# W682X.net
KiCad netlist of a schematic drawn in EAGLE
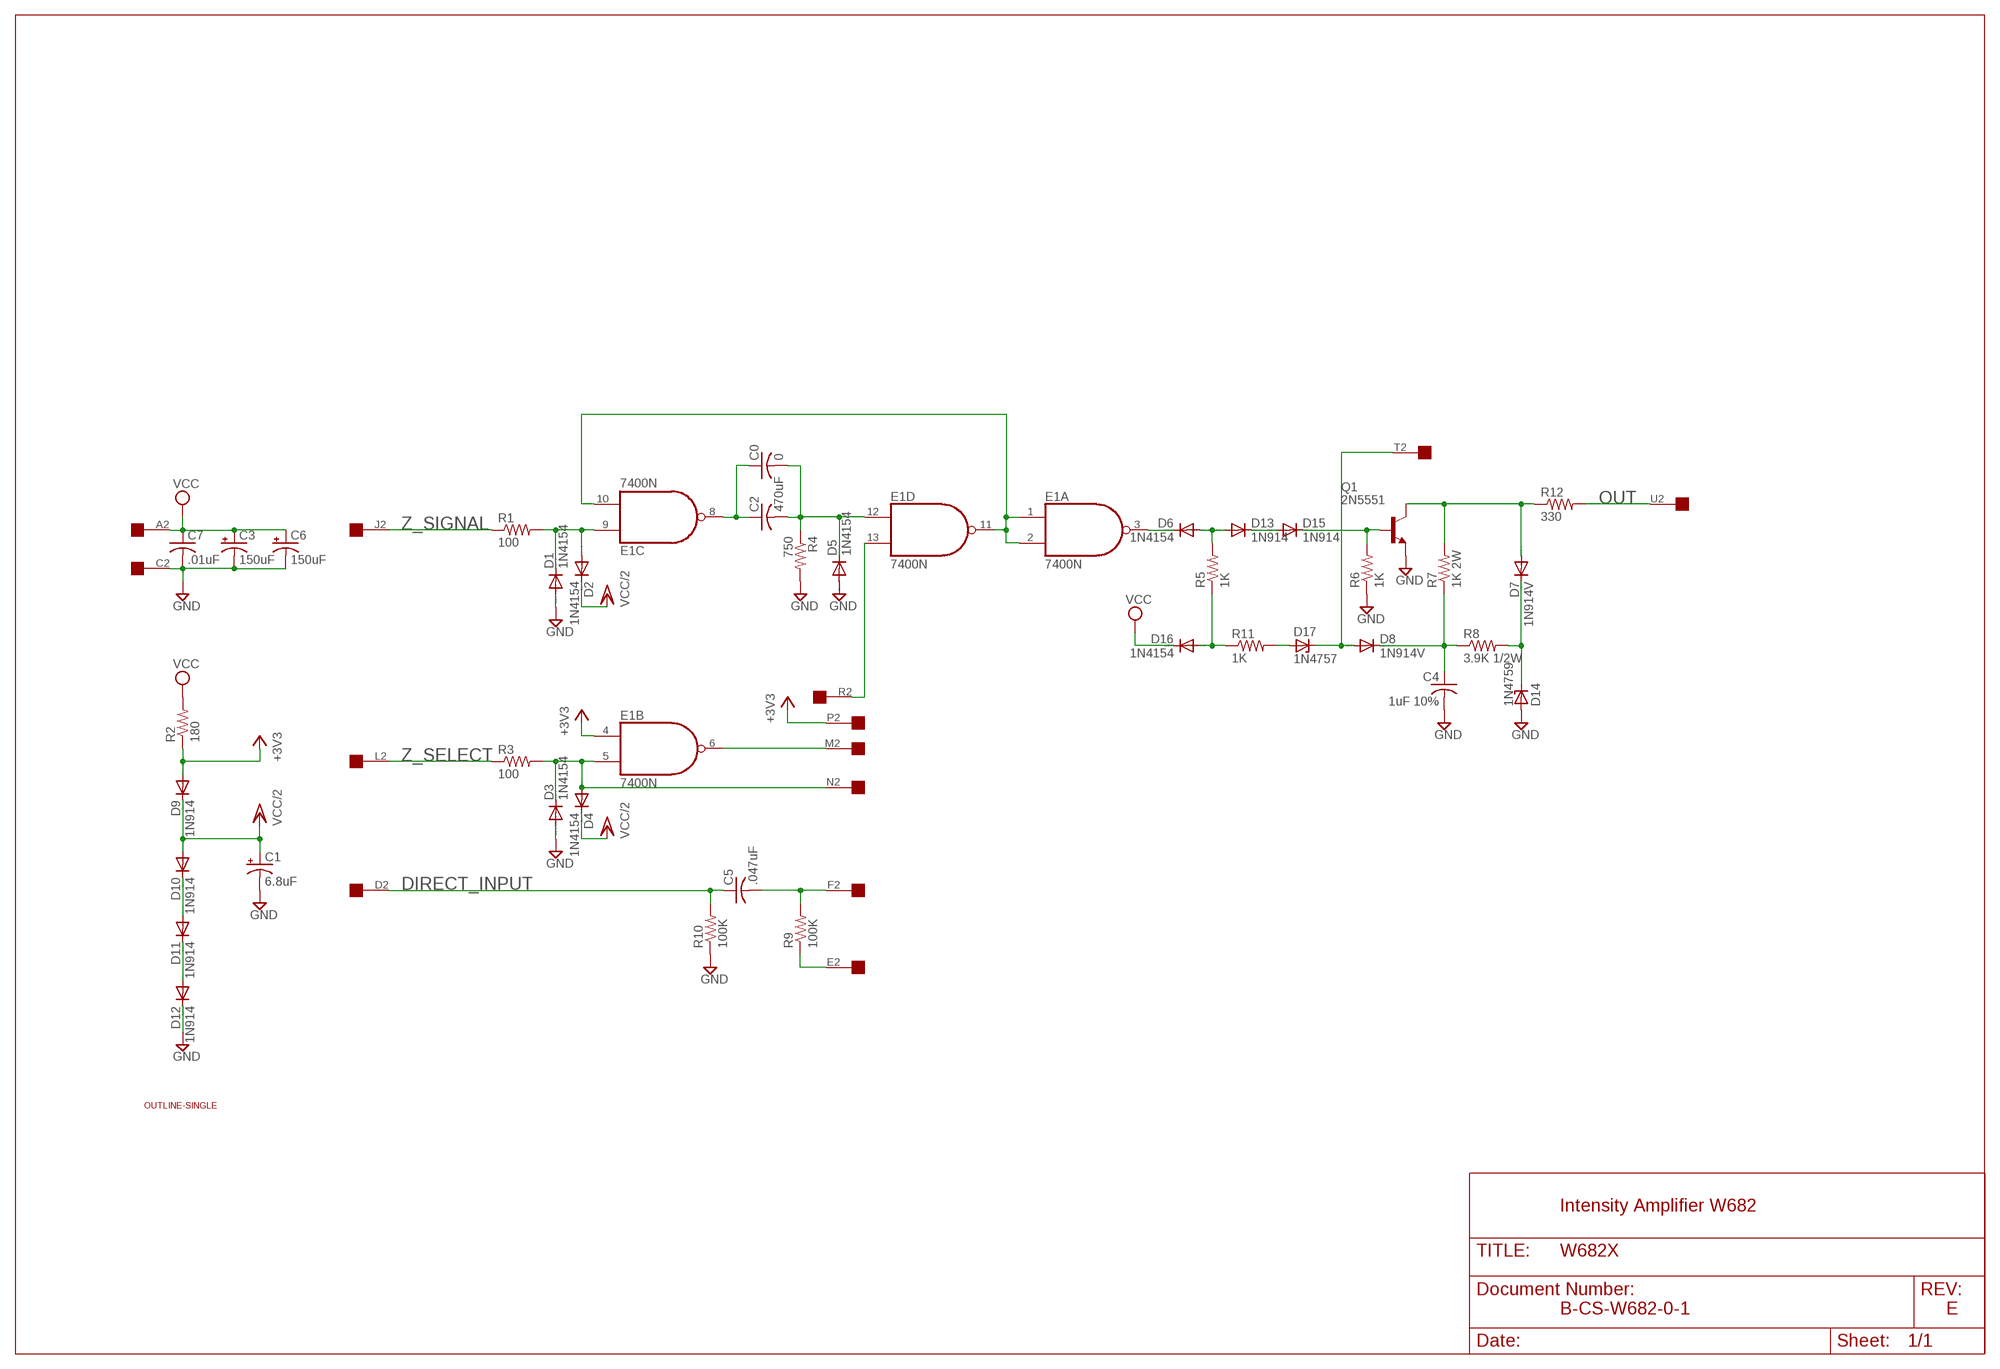
[diagram p0: schematic, sheet 1]

(export (version "E")
  (design (tool "Eeschema 10.0.6"))
  (components
    (comp (ref "C0")
      (value "0")
      (footprint "eagle-import:C050-025X075")
      (libsource (lib "eagle-import") (part "C-US050-025X075"))
    )
    (comp (ref "C1")
      (value "6.8uF")
      (footprint "eagle-import:E12-8")
      (libsource (lib "eagle-import") (part "CPOL-USE20-8AXIAL"))
    )
    (comp (ref "C2")
      (value "470uF")
      (footprint "eagle-import:C050-025X075")
      (libsource (lib "eagle-import") (part "C-US050-025X075"))
    )
    (comp (ref "C3")
      (value "150uF")
      (footprint "eagle-import:E22-9")
      (libsource (lib "eagle-import") (part "CPOL-USE22-9AXIAL"))
    )
    (comp (ref "C4")
      (value "1uF 10%")
      (footprint "eagle-import:C325-137X374")
      (libsource (lib "eagle-import") (part "C-US325-137X374"))
    )
    (comp (ref "C5")
      (value ".047uF")
      (footprint "eagle-import:C275-093X316")
      (libsource (lib "eagle-import") (part "C-US275-093X316"))
    )
    (comp (ref "C6")
      (value "150uF")
      (footprint "eagle-import:E22-9")
      (libsource (lib "eagle-import") (part "CPOL-USE22-9AXIAL"))
    )
    (comp (ref "C7")
      (value ".01uF")
      (footprint "eagle-import:C050-025X075")
      (libsource (lib "eagle-import") (part "C-US050-025X075"))
    )
    (comp (ref "D1")
      (value "1N4154")
      (footprint "eagle-import:DO35-10")
      (libsource (lib "eagle-import") (part "DIODE-DO35-10"))
    )
    (comp (ref "D2")
      (value "1N4154")
      (footprint "eagle-import:DO35-10")
      (libsource (lib "eagle-import") (part "DIODE-DO35-10"))
    )
    (comp (ref "D3")
      (value "1N4154")
      (footprint "eagle-import:DO35-10")
      (libsource (lib "eagle-import") (part "DIODE-DO35-10"))
    )
    (comp (ref "D4")
      (value "1N4154")
      (footprint "eagle-import:DO35-10")
      (libsource (lib "eagle-import") (part "DIODE-DO35-10"))
    )
    (comp (ref "D5")
      (value "1N4154")
      (footprint "eagle-import:DO35-10")
      (libsource (lib "eagle-import") (part "DIODE-DO35-10"))
    )
    (comp (ref "D6")
      (value "1N4154")
      (footprint "eagle-import:DO35-10")
      (libsource (lib "eagle-import") (part "DIODE-DO35-10"))
    )
    (comp (ref "D7")
      (value "1N914V")
      (footprint "eagle-import:DO41-10")
      (libsource (lib "eagle-import") (part "DIODE-DO41-10"))
    )
    (comp (ref "D8")
      (value "1N914V")
      (footprint "eagle-import:DO41-10")
      (libsource (lib "eagle-import") (part "DIODE-DO41-10"))
    )
    (comp (ref "D9")
      (value "1N914")
      (footprint "eagle-import:DO35-10")
      (libsource (lib "eagle-import") (part "DIODE-DO35-10"))
    )
    (comp (ref "D10")
      (value "1N914")
      (footprint "eagle-import:DO35-10")
      (libsource (lib "eagle-import") (part "DIODE-DO35-10"))
    )
    (comp (ref "D11")
      (value "1N914")
      (footprint "eagle-import:DO35-10")
      (libsource (lib "eagle-import") (part "DIODE-DO35-10"))
    )
    (comp (ref "D12")
      (value "1N914")
      (footprint "eagle-import:DO35-10")
      (libsource (lib "eagle-import") (part "DIODE-DO35-10"))
    )
    (comp (ref "D13")
      (value "1N914")
      (footprint "eagle-import:DO35-10")
      (libsource (lib "eagle-import") (part "DIODE-DO35-10"))
    )
    (comp (ref "D14")
      (value "1N4759")
      (footprint "eagle-import:ZDIO12.5")
      (libsource (lib "eagle-import") (part "ZENER-DIODEZD-12.5"))
    )
    (comp (ref "D15")
      (value "1N914")
      (footprint "eagle-import:DO35-10")
      (libsource (lib "eagle-import") (part "DIODE-DO35-10"))
    )
    (comp (ref "D16")
      (value "1N4154")
      (footprint "eagle-import:DO35-10")
      (libsource (lib "eagle-import") (part "DIODE-DO35-10"))
    )
    (comp (ref "D17")
      (value "1N4757")
      (footprint "eagle-import:ZDIO12.5")
      (libsource (lib "eagle-import") (part "ZENER-DIODEZD-12.5"))
    )
    (comp (ref "E1")
      (value "7400N")
      (footprint "eagle-import:DIL14")
      (libsource (lib "eagle-import") (part "7400N"))
    )
    (comp (ref "Q1")
      (value "2N5551")
      (footprint "eagle-import:TO39")
      (libsource (lib "eagle-import") (part "-NPN-TO39-EBC2N2102"))
    )
    (comp (ref "R1")
      (value "100")
      (footprint "eagle-import:0207_10")
      (libsource (lib "eagle-import") (part "R-US_0207/10"))
    )
    (comp (ref "R2")
      (value "180")
      (footprint "eagle-import:0207_10")
      (libsource (lib "eagle-import") (part "R-US_0207/10"))
    )
    (comp (ref "R3")
      (value "100")
      (footprint "eagle-import:0207_10")
      (libsource (lib "eagle-import") (part "R-US_0207/10"))
    )
    (comp (ref "R4")
      (value "750")
      (footprint "eagle-import:0207_10")
      (libsource (lib "eagle-import") (part "R-US_0207/10"))
    )
    (comp (ref "R5")
      (value "1K")
      (footprint "eagle-import:0207_10")
      (libsource (lib "eagle-import") (part "R-US_0207/10"))
    )
    (comp (ref "R6")
      (value "1K")
      (footprint "eagle-import:0207_10")
      (libsource (lib "eagle-import") (part "R-US_0207/10"))
    )
    (comp (ref "R7")
      (value "1K 2W")
      (footprint "eagle-import:0818_25")
      (libsource (lib "eagle-import") (part "R-US_0818/25"))
    )
    (comp (ref "R8")
      (value "3.9K 1/2W")
      (footprint "eagle-import:0411_15")
      (libsource (lib "eagle-import") (part "R-US_0411/15"))
    )
    (comp (ref "R9")
      (value "100K")
      (footprint "eagle-import:0207_10")
      (libsource (lib "eagle-import") (part "R-US_0207/10"))
    )
    (comp (ref "R10")
      (value "100K")
      (footprint "eagle-import:0207_10")
      (libsource (lib "eagle-import") (part "R-US_0207/10"))
    )
    (comp (ref "R11")
      (value "1K")
      (footprint "eagle-import:0207_10")
      (libsource (lib "eagle-import") (part "R-US_0207/10"))
    )
    (comp (ref "R12")
      (value "330")
      (footprint "eagle-import:0207_10")
      (libsource (lib "eagle-import") (part "R-US_0207/10"))
    )
    (comp (ref "U$1")
      (value "OUTLINE-SINGLE")
      (footprint "eagle-import:SINGLE")
      (libsource (lib "eagle-import") (part "OUTLINE-SINGLE"))
    )
    (comp (ref "U$2")
      (value "EDGE-1")
      (footprint "eagle-import:EDGE-CON1")
      (libsource (lib "eagle-import") (part "EDGE-1"))
    )
  )
  (nets
    (net (code "1") (name "+3V3") (class "Default")
      (node (ref "D9") (pin "A") (pinfunction "A_A") (pintype "passive"))
      (node (ref "E1") (pin "4") (pinfunction "I0_4") (pintype "input"))
      (node (ref "R2") (pin "1") (pinfunction "1_1") (pintype "passive"))
      (node (ref "U$2") (pin "P2") (pinfunction "1_P2") (pintype "bidirectional"))
    )
    (net (code "2") (name "/DIRECT_INPUT") (class "Default")
      (node (ref "C5") (pin "1") (pinfunction "1_1") (pintype "passive"))
      (node (ref "R10") (pin "2") (pinfunction "2_2") (pintype "passive"))
      (node (ref "U$2") (pin "D2") (pinfunction "1_D2") (pintype "bidirectional"))
    )
    (net (code "3") (name "/OUT") (class "Default")
      (node (ref "R12") (pin "2") (pinfunction "2_2") (pintype "passive"))
      (node (ref "U$2") (pin "U2") (pinfunction "1_U2") (pintype "bidirectional"))
    )
    (net (code "4") (name "/Z_SELECT") (class "Default")
      (node (ref "R3") (pin "1") (pinfunction "1_1") (pintype "passive"))
      (node (ref "U$2") (pin "L2") (pinfunction "1_L2") (pintype "bidirectional"))
    )
    (net (code "5") (name "/Z_SIGNAL") (class "Default")
      (node (ref "R1") (pin "1") (pinfunction "1_1") (pintype "passive"))
      (node (ref "U$2") (pin "J2") (pinfunction "1_J2") (pintype "bidirectional"))
    )
    (net (code "6") (name "GND") (class "Default")
      (node (ref "C1") (pin "-") (pinfunction "-_-") (pintype "passive"))
      (node (ref "C3") (pin "-") (pinfunction "-_-") (pintype "passive"))
      (node (ref "C4") (pin "2") (pinfunction "2_2") (pintype "passive"))
      (node (ref "C6") (pin "-") (pinfunction "-_-") (pintype "passive"))
      (node (ref "C7") (pin "2") (pinfunction "2_2") (pintype "passive"))
      (node (ref "D1") (pin "A") (pinfunction "A_A") (pintype "passive"))
      (node (ref "D12") (pin "C") (pinfunction "C_C") (pintype "passive"))
      (node (ref "D14") (pin "A") (pinfunction "A_A") (pintype "passive"))
      (node (ref "D3") (pin "A") (pinfunction "A_A") (pintype "passive"))
      (node (ref "D5") (pin "A") (pinfunction "A_A") (pintype "passive"))
      (node (ref "Q1") (pin "1") (pinfunction "E_1") (pintype "passive"))
      (node (ref "R10") (pin "1") (pinfunction "1_1") (pintype "passive"))
      (node (ref "R4") (pin "2") (pinfunction "2_2") (pintype "passive"))
      (node (ref "R6") (pin "1") (pinfunction "1_1") (pintype "passive"))
      (node (ref "U$2") (pin "C2") (pinfunction "1_C2") (pintype "bidirectional"))
    )
    (net (code "7") (name "Net-(C4-Pad1)") (class "Default")
      (node (ref "C4") (pin "1") (pinfunction "1_1") (pintype "passive"))
      (node (ref "D8") (pin "C") (pinfunction "C_C") (pintype "passive"))
      (node (ref "R7") (pin "1") (pinfunction "1_1") (pintype "passive"))
      (node (ref "R8") (pin "1") (pinfunction "1_1") (pintype "passive"))
    )
    (net (code "8") (name "Net-(D10-PadC)") (class "Default")
      (node (ref "D10") (pin "C") (pinfunction "C_C") (pintype "passive"))
      (node (ref "D11") (pin "A") (pinfunction "A_A") (pintype "passive"))
    )
    (net (code "9") (name "Net-(D11-PadC)") (class "Default")
      (node (ref "D11") (pin "C") (pinfunction "C_C") (pintype "passive"))
      (node (ref "D12") (pin "A") (pinfunction "A_A") (pintype "passive"))
    )
    (net (code "10") (name "Net-(D13-PadA)") (class "Default")
      (node (ref "D13") (pin "A") (pinfunction "A_A") (pintype "passive"))
      (node (ref "D6") (pin "A") (pinfunction "A_A") (pintype "passive"))
      (node (ref "R5") (pin "2") (pinfunction "2_2") (pintype "passive"))
    )
    (net (code "11") (name "Net-(D13-PadC)") (class "Default")
      (node (ref "D13") (pin "C") (pinfunction "C_C") (pintype "passive"))
      (node (ref "D15") (pin "A") (pinfunction "A_A") (pintype "passive"))
    )
    (net (code "12") (name "Net-(D14-PadC)") (class "Default")
      (node (ref "D14") (pin "C") (pinfunction "C_C") (pintype "passive"))
      (node (ref "D7") (pin "C") (pinfunction "C_C") (pintype "passive"))
      (node (ref "R8") (pin "2") (pinfunction "2_2") (pintype "passive"))
    )
    (net (code "13") (name "Net-(D16-PadA)") (class "Default")
      (node (ref "D16") (pin "A") (pinfunction "A_A") (pintype "passive"))
      (node (ref "R11") (pin "1") (pinfunction "1_1") (pintype "passive"))
      (node (ref "R5") (pin "1") (pinfunction "1_1") (pintype "passive"))
    )
    (net (code "14") (name "Net-(D17-PadA)") (class "Default")
      (node (ref "D17") (pin "A") (pinfunction "A_A") (pintype "passive"))
      (node (ref "R11") (pin "2") (pinfunction "2_2") (pintype "passive"))
    )
    (net (code "15") (name "Net-(E1A-I0)") (class "Default")
      (node (ref "E1") (pin "1") (pinfunction "I0_1") (pintype "input"))
      (node (ref "E1") (pin "10") (pinfunction "I1_10") (pintype "input"))
      (node (ref "E1") (pin "11") (pinfunction "O_11") (pintype "output"))
      (node (ref "E1") (pin "2") (pinfunction "I1_2") (pintype "input"))
    )
    (net (code "16") (name "Net-(E1A-O)") (class "Default")
      (node (ref "D6") (pin "C") (pinfunction "C_C") (pintype "passive"))
      (node (ref "E1") (pin "3") (pinfunction "O_3") (pintype "output"))
    )
    (net (code "17") (name "Net-(E1B-I1)") (class "Default")
      (node (ref "D3") (pin "C") (pinfunction "C_C") (pintype "passive"))
      (node (ref "D4") (pin "A") (pinfunction "A_A") (pintype "passive"))
      (node (ref "E1") (pin "5") (pinfunction "I1_5") (pintype "input"))
      (node (ref "R3") (pin "2") (pinfunction "2_2") (pintype "passive"))
      (node (ref "U$2") (pin "N2") (pinfunction "1_N2") (pintype "bidirectional"))
    )
    (net (code "18") (name "Net-(E1B-O)") (class "Default")
      (node (ref "E1") (pin "6") (pinfunction "O_6") (pintype "output"))
      (node (ref "U$2") (pin "M2") (pinfunction "1_M2") (pintype "bidirectional"))
    )
    (net (code "19") (name "Net-(E1C-I0)") (class "Default")
      (node (ref "D1") (pin "C") (pinfunction "C_C") (pintype "passive"))
      (node (ref "D2") (pin "A") (pinfunction "A_A") (pintype "passive"))
      (node (ref "E1") (pin "9") (pinfunction "I0_9") (pintype "input"))
      (node (ref "R1") (pin "2") (pinfunction "2_2") (pintype "passive"))
    )
    (net (code "20") (name "Net-(E1C-O)") (class "Default")
      (node (ref "C0") (pin "1") (pinfunction "1_1") (pintype "passive"))
      (node (ref "C2") (pin "1") (pinfunction "1_1") (pintype "passive"))
      (node (ref "E1") (pin "8") (pinfunction "O_8") (pintype "output"))
    )
    (net (code "21") (name "Net-(E1D-I0)") (class "Default")
      (node (ref "C0") (pin "2") (pinfunction "2_2") (pintype "passive"))
      (node (ref "C2") (pin "2") (pinfunction "2_2") (pintype "passive"))
      (node (ref "D5") (pin "C") (pinfunction "C_C") (pintype "passive"))
      (node (ref "E1") (pin "12") (pinfunction "I0_12") (pintype "input"))
      (node (ref "R4") (pin "1") (pinfunction "1_1") (pintype "passive"))
    )
    (net (code "22") (name "Net-(E1D-I1)") (class "Default")
      (node (ref "E1") (pin "13") (pinfunction "I1_13") (pintype "input"))
      (node (ref "U$2") (pin "R2") (pinfunction "1_R2") (pintype "bidirectional"))
    )
    (net (code "23") (name "Net-(Q1-B)") (class "Default")
      (node (ref "D15") (pin "C") (pinfunction "C_C") (pintype "passive"))
      (node (ref "Q1") (pin "2") (pinfunction "B_2") (pintype "passive"))
      (node (ref "R6") (pin "2") (pinfunction "2_2") (pintype "passive"))
    )
    (net (code "24") (name "Net-(Q1-C)") (class "Default")
      (node (ref "D7") (pin "A") (pinfunction "A_A") (pintype "passive"))
      (node (ref "Q1") (pin "3") (pinfunction "C_3") (pintype "passive"))
      (node (ref "R12") (pin "1") (pinfunction "1_1") (pintype "passive"))
      (node (ref "R7") (pin "2") (pinfunction "2_2") (pintype "passive"))
    )
    (net (code "25") (name "Net-(U$2E-1)") (class "Default")
      (node (ref "R9") (pin "1") (pinfunction "1_1") (pintype "passive"))
      (node (ref "U$2") (pin "E2") (pinfunction "1_E2") (pintype "bidirectional"))
    )
    (net (code "26") (name "Net-(U$2F-1)") (class "Default")
      (node (ref "C5") (pin "2") (pinfunction "2_2") (pintype "passive"))
      (node (ref "R9") (pin "2") (pinfunction "2_2") (pintype "passive"))
      (node (ref "U$2") (pin "F2") (pinfunction "1_F2") (pintype "bidirectional"))
    )
    (net (code "27") (name "Net-(U$2P-1)") (class "Default")
      (node (ref "D17") (pin "C") (pinfunction "C_C") (pintype "passive"))
      (node (ref "D8") (pin "A") (pinfunction "A_A") (pintype "passive"))
      (node (ref "U$2") (pin "T2") (pinfunction "1_T2") (pintype "bidirectional"))
    )
    (net (code "28") (name "VCC") (class "Default")
      (node (ref "C3") (pin "+") (pinfunction "+_+") (pintype "passive"))
      (node (ref "C6") (pin "+") (pinfunction "+_+") (pintype "passive"))
      (node (ref "C7") (pin "1") (pinfunction "1_1") (pintype "passive"))
      (node (ref "D16") (pin "C") (pinfunction "C_C") (pintype "passive"))
      (node (ref "R2") (pin "2") (pinfunction "2_2") (pintype "passive"))
      (node (ref "U$2") (pin "A2") (pinfunction "1_A2") (pintype "bidirectional"))
    )
    (net (code "29") (name "VCC{slash}2") (class "Default")
      (node (ref "C1") (pin "+") (pinfunction "+_+") (pintype "passive"))
      (node (ref "D10") (pin "A") (pinfunction "A_A") (pintype "passive"))
      (node (ref "D2") (pin "C") (pinfunction "C_C") (pintype "passive"))
      (node (ref "D4") (pin "C") (pinfunction "C_C") (pintype "passive"))
      (node (ref "D9") (pin "C") (pinfunction "C_C") (pintype "passive"))
    )
  )
)
